# ARC_Lighting_v1_2.net
KiCad netlist of a schematic drawn in EAGLE
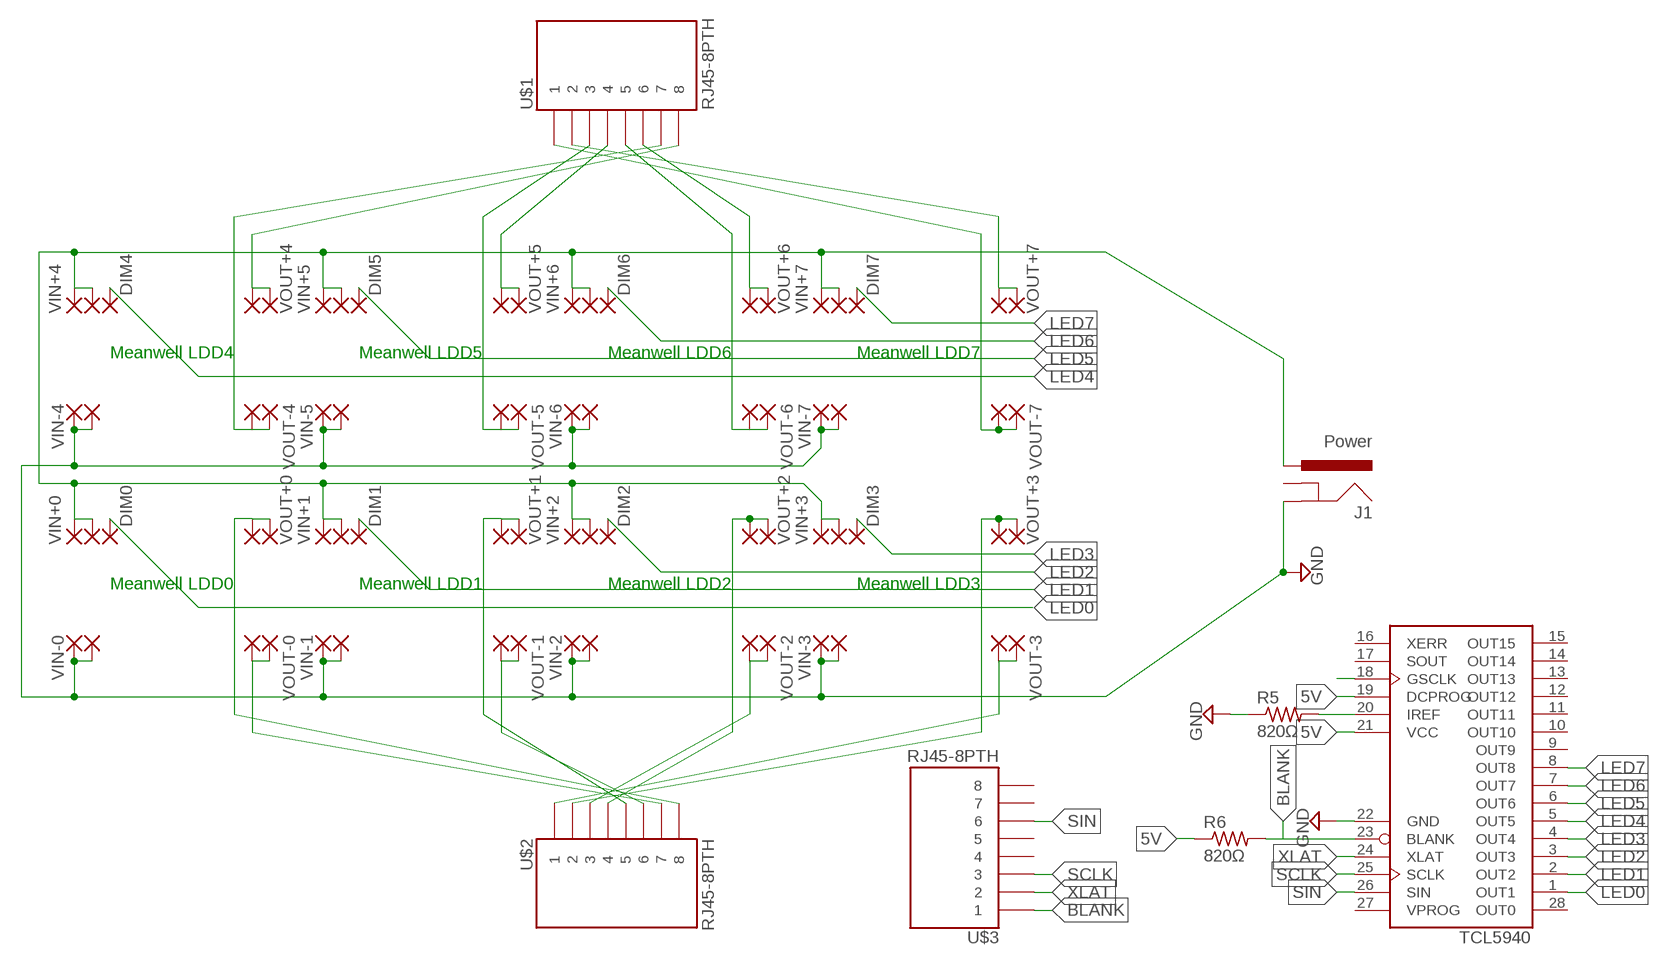
[diagram p0: schematic, sheet 1]

(export (version "E")
  (design (tool "Eeschema 10.0.6"))
  (components
    (comp (ref "DIM0")
      (value "2,15/1,0")
      (footprint "eagle-import:2,15_1,0")
      (libsource (lib "eagle-import") (part "2,15/1,0"))
    )
    (comp (ref "DIM1")
      (value "2,15/1,0")
      (footprint "eagle-import:2,15_1,0")
      (libsource (lib "eagle-import") (part "2,15/1,0"))
    )
    (comp (ref "DIM2")
      (value "2,15/1,0")
      (footprint "eagle-import:2,15_1,0")
      (libsource (lib "eagle-import") (part "2,15/1,0"))
    )
    (comp (ref "DIM3")
      (value "2,15/1,0")
      (footprint "eagle-import:2,15_1,0")
      (libsource (lib "eagle-import") (part "2,15/1,0"))
    )
    (comp (ref "DIM4")
      (value "2,15/1,0")
      (footprint "eagle-import:2,15_1,0")
      (libsource (lib "eagle-import") (part "2,15/1,0"))
    )
    (comp (ref "DIM5")
      (value "2,15/1,0")
      (footprint "eagle-import:2,15_1,0")
      (libsource (lib "eagle-import") (part "2,15/1,0"))
    )
    (comp (ref "DIM6")
      (value "2,15/1,0")
      (footprint "eagle-import:2,15_1,0")
      (libsource (lib "eagle-import") (part "2,15/1,0"))
    )
    (comp (ref "DIM7")
      (value "2,15/1,0")
      (footprint "eagle-import:2,15_1,0")
      (libsource (lib "eagle-import") (part "2,15/1,0"))
    )
    (comp (ref "I+0")
      (value "2,15/1,0")
      (footprint "eagle-import:2,15_1,0")
      (libsource (lib "eagle-import") (part "2,15/1,0"))
    )
    (comp (ref "I+1")
      (value "2,15/1,0")
      (footprint "eagle-import:2,15_1,0")
      (libsource (lib "eagle-import") (part "2,15/1,0"))
    )
    (comp (ref "I+2")
      (value "2,15/1,0")
      (footprint "eagle-import:2,15_1,0")
      (libsource (lib "eagle-import") (part "2,15/1,0"))
    )
    (comp (ref "I+3")
      (value "2,15/1,0")
      (footprint "eagle-import:2,15_1,0")
      (libsource (lib "eagle-import") (part "2,15/1,0"))
    )
    (comp (ref "I+4")
      (value "2,15/1,0")
      (footprint "eagle-import:2,15_1,0")
      (libsource (lib "eagle-import") (part "2,15/1,0"))
    )
    (comp (ref "I+5")
      (value "2,15/1,0")
      (footprint "eagle-import:2,15_1,0")
      (libsource (lib "eagle-import") (part "2,15/1,0"))
    )
    (comp (ref "I+6")
      (value "2,15/1,0")
      (footprint "eagle-import:2,15_1,0")
      (libsource (lib "eagle-import") (part "2,15/1,0"))
    )
    (comp (ref "I+7")
      (value "2,15/1,0")
      (footprint "eagle-import:2,15_1,0")
      (libsource (lib "eagle-import") (part "2,15/1,0"))
    )
    (comp (ref "I-0")
      (value "2,15/1,0")
      (footprint "eagle-import:2,15_1,0")
      (libsource (lib "eagle-import") (part "2,15/1,0"))
    )
    (comp (ref "I-1")
      (value "2,15/1,0")
      (footprint "eagle-import:2,15_1,0")
      (libsource (lib "eagle-import") (part "2,15/1,0"))
    )
    (comp (ref "I-2")
      (value "2,15/1,0")
      (footprint "eagle-import:2,15_1,0")
      (libsource (lib "eagle-import") (part "2,15/1,0"))
    )
    (comp (ref "I-3")
      (value "2,15/1,0")
      (footprint "eagle-import:2,15_1,0")
      (libsource (lib "eagle-import") (part "2,15/1,0"))
    )
    (comp (ref "I-4")
      (value "2,15/1,0")
      (footprint "eagle-import:2,15_1,0")
      (libsource (lib "eagle-import") (part "2,15/1,0"))
    )
    (comp (ref "I-5")
      (value "2,15/1,0")
      (footprint "eagle-import:2,15_1,0")
      (libsource (lib "eagle-import") (part "2,15/1,0"))
    )
    (comp (ref "I-6")
      (value "2,15/1,0")
      (footprint "eagle-import:2,15_1,0")
      (libsource (lib "eagle-import") (part "2,15/1,0"))
    )
    (comp (ref "I-7")
      (value "2,15/1,0")
      (footprint "eagle-import:2,15_1,0")
      (libsource (lib "eagle-import") (part "2,15/1,0"))
    )
    (comp (ref "IC1")
      (value "TCL5940")
      (footprint "eagle-import:DIP28")
      (libsource (lib "eagle-import") (part "TCL5940"))
    )
    (comp (ref "J1")
      (value "Power")
      (footprint "eagle-import:POWER_JACK_PTH_BREAD")
      (libsource (lib "eagle-import") (part "POWER_JACKPTH_BREAD"))
    )
    (comp (ref "O+0")
      (value "2,15/1,0")
      (footprint "eagle-import:2,15_1,0")
      (libsource (lib "eagle-import") (part "2,15/1,0"))
    )
    (comp (ref "O+1")
      (value "2,15/1,0")
      (footprint "eagle-import:2,15_1,0")
      (libsource (lib "eagle-import") (part "2,15/1,0"))
    )
    (comp (ref "O+2")
      (value "2,15/1,0")
      (footprint "eagle-import:2,15_1,0")
      (libsource (lib "eagle-import") (part "2,15/1,0"))
    )
    (comp (ref "O+3")
      (value "2,15/1,0")
      (footprint "eagle-import:2,15_1,0")
      (libsource (lib "eagle-import") (part "2,15/1,0"))
    )
    (comp (ref "O+4")
      (value "2,15/1,0")
      (footprint "eagle-import:2,15_1,0")
      (libsource (lib "eagle-import") (part "2,15/1,0"))
    )
    (comp (ref "O+5")
      (value "2,15/1,0")
      (footprint "eagle-import:2,15_1,0")
      (libsource (lib "eagle-import") (part "2,15/1,0"))
    )
    (comp (ref "O+6")
      (value "2,15/1,0")
      (footprint "eagle-import:2,15_1,0")
      (libsource (lib "eagle-import") (part "2,15/1,0"))
    )
    (comp (ref "O+7")
      (value "2,15/1,0")
      (footprint "eagle-import:2,15_1,0")
      (libsource (lib "eagle-import") (part "2,15/1,0"))
    )
    (comp (ref "O-0")
      (value "2,15/1,0")
      (footprint "eagle-import:2,15_1,0")
      (libsource (lib "eagle-import") (part "2,15/1,0"))
    )
    (comp (ref "O-1")
      (value "2,15/1,0")
      (footprint "eagle-import:2,15_1,0")
      (libsource (lib "eagle-import") (part "2,15/1,0"))
    )
    (comp (ref "O-2")
      (value "2,15/1,0")
      (footprint "eagle-import:2,15_1,0")
      (libsource (lib "eagle-import") (part "2,15/1,0"))
    )
    (comp (ref "O-3")
      (value "2,15/1,0")
      (footprint "eagle-import:2,15_1,0")
      (libsource (lib "eagle-import") (part "2,15/1,0"))
    )
    (comp (ref "O-4")
      (value "2,15/1,0")
      (footprint "eagle-import:2,15_1,0")
      (libsource (lib "eagle-import") (part "2,15/1,0"))
    )
    (comp (ref "O-5")
      (value "2,15/1,0")
      (footprint "eagle-import:2,15_1,0")
      (libsource (lib "eagle-import") (part "2,15/1,0"))
    )
    (comp (ref "O-6")
      (value "2,15/1,0")
      (footprint "eagle-import:2,15_1,0")
      (libsource (lib "eagle-import") (part "2,15/1,0"))
    )
    (comp (ref "O-7")
      (value "2,15/1,0")
      (footprint "eagle-import:2,15_1,0")
      (libsource (lib "eagle-import") (part "2,15/1,0"))
    )
    (comp (ref "R5")
      (value "820Ω")
      (footprint "eagle-import:0204_7")
      (libsource (lib "eagle-import") (part "R-US_0204/7"))
    )
    (comp (ref "R6")
      (value "820Ω")
      (footprint "eagle-import:0204_7")
      (libsource (lib "eagle-import") (part "R-US_0204/7"))
    )
    (comp (ref "U$1")
      (value "RJ45-8PTH")
      (footprint "eagle-import:RJ45-8")
      (libsource (lib "eagle-import") (part "RJ45-8PTH"))
    )
    (comp (ref "U$2")
      (value "RJ45-8PTH")
      (footprint "eagle-import:RJ45-8")
      (libsource (lib "eagle-import") (part "RJ45-8PTH"))
    )
    (comp (ref "U$3")
      (value "RJ45-8PTH")
      (footprint "eagle-import:RJ45-8")
      (libsource (lib "eagle-import") (part "RJ45-8PTH"))
    )
    (comp (ref "VIN+0")
      (value "2,15/1,0")
      (footprint "eagle-import:2,15_1,0")
      (libsource (lib "eagle-import") (part "2,15/1,0"))
    )
    (comp (ref "VIN+1")
      (value "2,15/1,0")
      (footprint "eagle-import:2,15_1,0")
      (libsource (lib "eagle-import") (part "2,15/1,0"))
    )
    (comp (ref "VIN+2")
      (value "2,15/1,0")
      (footprint "eagle-import:2,15_1,0")
      (libsource (lib "eagle-import") (part "2,15/1,0"))
    )
    (comp (ref "VIN+3")
      (value "2,15/1,0")
      (footprint "eagle-import:2,15_1,0")
      (libsource (lib "eagle-import") (part "2,15/1,0"))
    )
    (comp (ref "VIN+4")
      (value "2,15/1,0")
      (footprint "eagle-import:2,15_1,0")
      (libsource (lib "eagle-import") (part "2,15/1,0"))
    )
    (comp (ref "VIN+5")
      (value "2,15/1,0")
      (footprint "eagle-import:2,15_1,0")
      (libsource (lib "eagle-import") (part "2,15/1,0"))
    )
    (comp (ref "VIN+6")
      (value "2,15/1,0")
      (footprint "eagle-import:2,15_1,0")
      (libsource (lib "eagle-import") (part "2,15/1,0"))
    )
    (comp (ref "VIN+7")
      (value "2,15/1,0")
      (footprint "eagle-import:2,15_1,0")
      (libsource (lib "eagle-import") (part "2,15/1,0"))
    )
    (comp (ref "VIN-0")
      (value "2,15/1,0")
      (footprint "eagle-import:2,15_1,0")
      (libsource (lib "eagle-import") (part "2,15/1,0"))
    )
    (comp (ref "VIN-1")
      (value "2,15/1,0")
      (footprint "eagle-import:2,15_1,0")
      (libsource (lib "eagle-import") (part "2,15/1,0"))
    )
    (comp (ref "VIN-2")
      (value "2,15/1,0")
      (footprint "eagle-import:2,15_1,0")
      (libsource (lib "eagle-import") (part "2,15/1,0"))
    )
    (comp (ref "VIN-3")
      (value "2,15/1,0")
      (footprint "eagle-import:2,15_1,0")
      (libsource (lib "eagle-import") (part "2,15/1,0"))
    )
    (comp (ref "VIN-4")
      (value "2,15/1,0")
      (footprint "eagle-import:2,15_1,0")
      (libsource (lib "eagle-import") (part "2,15/1,0"))
    )
    (comp (ref "VIN-5")
      (value "2,15/1,0")
      (footprint "eagle-import:2,15_1,0")
      (libsource (lib "eagle-import") (part "2,15/1,0"))
    )
    (comp (ref "VIN-6")
      (value "2,15/1,0")
      (footprint "eagle-import:2,15_1,0")
      (libsource (lib "eagle-import") (part "2,15/1,0"))
    )
    (comp (ref "VIN-7")
      (value "2,15/1,0")
      (footprint "eagle-import:2,15_1,0")
      (libsource (lib "eagle-import") (part "2,15/1,0"))
    )
    (comp (ref "VOUT+0")
      (value "2,15/1,0")
      (footprint "eagle-import:2,15_1,0")
      (libsource (lib "eagle-import") (part "2,15/1,0"))
    )
    (comp (ref "VOUT+1")
      (value "2,15/1,0")
      (footprint "eagle-import:2,15_1,0")
      (libsource (lib "eagle-import") (part "2,15/1,0"))
    )
    (comp (ref "VOUT+2")
      (value "2,15/1,0")
      (footprint "eagle-import:2,15_1,0")
      (libsource (lib "eagle-import") (part "2,15/1,0"))
    )
    (comp (ref "VOUT+3")
      (value "2,15/1,0")
      (footprint "eagle-import:2,15_1,0")
      (libsource (lib "eagle-import") (part "2,15/1,0"))
    )
    (comp (ref "VOUT+4")
      (value "2,15/1,0")
      (footprint "eagle-import:2,15_1,0")
      (libsource (lib "eagle-import") (part "2,15/1,0"))
    )
    (comp (ref "VOUT+5")
      (value "2,15/1,0")
      (footprint "eagle-import:2,15_1,0")
      (libsource (lib "eagle-import") (part "2,15/1,0"))
    )
    (comp (ref "VOUT+6")
      (value "2,15/1,0")
      (footprint "eagle-import:2,15_1,0")
      (libsource (lib "eagle-import") (part "2,15/1,0"))
    )
    (comp (ref "VOUT+7")
      (value "2,15/1,0")
      (footprint "eagle-import:2,15_1,0")
      (libsource (lib "eagle-import") (part "2,15/1,0"))
    )
    (comp (ref "VOUT-0")
      (value "2,15/1,0")
      (footprint "eagle-import:2,15_1,0")
      (libsource (lib "eagle-import") (part "2,15/1,0"))
    )
    (comp (ref "VOUT-1")
      (value "2,15/1,0")
      (footprint "eagle-import:2,15_1,0")
      (libsource (lib "eagle-import") (part "2,15/1,0"))
    )
    (comp (ref "VOUT-2")
      (value "2,15/1,0")
      (footprint "eagle-import:2,15_1,0")
      (libsource (lib "eagle-import") (part "2,15/1,0"))
    )
    (comp (ref "VOUT-3")
      (value "2,15/1,0")
      (footprint "eagle-import:2,15_1,0")
      (libsource (lib "eagle-import") (part "2,15/1,0"))
    )
    (comp (ref "VOUT-4")
      (value "2,15/1,0")
      (footprint "eagle-import:2,15_1,0")
      (libsource (lib "eagle-import") (part "2,15/1,0"))
    )
    (comp (ref "VOUT-5")
      (value "2,15/1,0")
      (footprint "eagle-import:2,15_1,0")
      (libsource (lib "eagle-import") (part "2,15/1,0"))
    )
    (comp (ref "VOUT-6")
      (value "2,15/1,0")
      (footprint "eagle-import:2,15_1,0")
      (libsource (lib "eagle-import") (part "2,15/1,0"))
    )
    (comp (ref "VOUT-7")
      (value "2,15/1,0")
      (footprint "eagle-import:2,15_1,0")
      (libsource (lib "eagle-import") (part "2,15/1,0"))
    )
  )
  (nets
    (net (code "1") (name "5V") (class "Default")
      (node (ref "IC1") (pin "19") (pinfunction "DCPROG_19") (pintype "input"))
      (node (ref "IC1") (pin "21") (pinfunction "VCC_21") (pintype "power_in"))
      (node (ref "R6") (pin "1") (pinfunction "1_1") (pintype "passive"))
    )
    (net (code "2") (name "BLANK") (class "Default")
      (node (ref "IC1") (pin "23") (pinfunction "BLANK_23") (pintype "input"))
      (node (ref "R6") (pin "2") (pinfunction "2_2") (pintype "passive"))
      (node (ref "U$3") (pin "1") (pinfunction "1_1") (pintype "bidirectional"))
    )
    (net (code "3") (name "GND") (class "Default")
      (node (ref "I-0") (pin "1") (pinfunction "P_1") (pintype "passive"))
      (node (ref "I-1") (pin "1") (pinfunction "P_1") (pintype "passive"))
      (node (ref "I-2") (pin "1") (pinfunction "P_1") (pintype "passive"))
      (node (ref "I-3") (pin "1") (pinfunction "P_1") (pintype "passive"))
      (node (ref "I-4") (pin "1") (pinfunction "P_1") (pintype "passive"))
      (node (ref "I-5") (pin "1") (pinfunction "P_1") (pintype "passive"))
      (node (ref "I-6") (pin "1") (pinfunction "P_1") (pintype "passive"))
      (node (ref "I-7") (pin "1") (pinfunction "P_1") (pintype "passive"))
      (node (ref "IC1") (pin "22") (pinfunction "GND_22") (pintype "power_in"))
      (node (ref "J1") (pin "GND") (pinfunction "GND_GND") (pintype "bidirectional"))
      (node (ref "R5") (pin "1") (pinfunction "1_1") (pintype "passive"))
      (node (ref "VIN-0") (pin "1") (pinfunction "P_1") (pintype "passive"))
      (node (ref "VIN-1") (pin "1") (pinfunction "P_1") (pintype "passive"))
      (node (ref "VIN-2") (pin "1") (pinfunction "P_1") (pintype "passive"))
      (node (ref "VIN-3") (pin "1") (pinfunction "P_1") (pintype "passive"))
      (node (ref "VIN-4") (pin "1") (pinfunction "P_1") (pintype "passive"))
      (node (ref "VIN-5") (pin "1") (pinfunction "P_1") (pintype "passive"))
      (node (ref "VIN-6") (pin "1") (pinfunction "P_1") (pintype "passive"))
      (node (ref "VIN-7") (pin "1") (pinfunction "P_1") (pintype "passive"))
    )
    (net (code "4") (name "LED0") (class "Default")
      (node (ref "DIM0") (pin "1") (pinfunction "P_1") (pintype "passive"))
      (node (ref "IC1") (pin "1") (pinfunction "OUT1_1") (pintype "output"))
    )
    (net (code "5") (name "LED1") (class "Default")
      (node (ref "DIM1") (pin "1") (pinfunction "P_1") (pintype "passive"))
      (node (ref "IC1") (pin "2") (pinfunction "OUT2_2") (pintype "output"))
    )
    (net (code "6") (name "LED2") (class "Default")
      (node (ref "DIM2") (pin "1") (pinfunction "P_1") (pintype "passive"))
      (node (ref "IC1") (pin "3") (pinfunction "OUT3_3") (pintype "output"))
    )
    (net (code "7") (name "LED3") (class "Default")
      (node (ref "DIM3") (pin "1") (pinfunction "P_1") (pintype "passive"))
      (node (ref "IC1") (pin "4") (pinfunction "OUT4_4") (pintype "output"))
    )
    (net (code "8") (name "LED4") (class "Default")
      (node (ref "DIM4") (pin "1") (pinfunction "P_1") (pintype "passive"))
      (node (ref "IC1") (pin "5") (pinfunction "OUT5_5") (pintype "output"))
    )
    (net (code "9") (name "LED5") (class "Default")
      (node (ref "DIM5") (pin "1") (pinfunction "P_1") (pintype "passive"))
      (node (ref "IC1") (pin "6") (pinfunction "OUT6_6") (pintype "output"))
    )
    (net (code "10") (name "LED6") (class "Default")
      (node (ref "DIM6") (pin "1") (pinfunction "P_1") (pintype "passive"))
      (node (ref "IC1") (pin "7") (pinfunction "OUT7_7") (pintype "output"))
    )
    (net (code "11") (name "LED7") (class "Default")
      (node (ref "DIM7") (pin "1") (pinfunction "P_1") (pintype "passive"))
      (node (ref "IC1") (pin "8") (pinfunction "OUT8_8") (pintype "output"))
    )
    (net (code "12") (name "Net-(I+0-P)") (class "Default")
      (node (ref "I+0") (pin "1") (pinfunction "P_1") (pintype "passive"))
      (node (ref "I+1") (pin "1") (pinfunction "P_1") (pintype "passive"))
      (node (ref "I+2") (pin "1") (pinfunction "P_1") (pintype "passive"))
      (node (ref "I+3") (pin "1") (pinfunction "P_1") (pintype "passive"))
      (node (ref "I+4") (pin "1") (pinfunction "P_1") (pintype "passive"))
      (node (ref "I+5") (pin "1") (pinfunction "P_1") (pintype "passive"))
      (node (ref "I+6") (pin "1") (pinfunction "P_1") (pintype "passive"))
      (node (ref "I+7") (pin "1") (pinfunction "P_1") (pintype "passive"))
      (node (ref "J1") (pin "PWR") (pinfunction "PWR_PWR") (pintype "bidirectional"))
      (node (ref "VIN+0") (pin "1") (pinfunction "P_1") (pintype "passive"))
      (node (ref "VIN+1") (pin "1") (pinfunction "P_1") (pintype "passive"))
      (node (ref "VIN+2") (pin "1") (pinfunction "P_1") (pintype "passive"))
      (node (ref "VIN+3") (pin "1") (pinfunction "P_1") (pintype "passive"))
      (node (ref "VIN+4") (pin "1") (pinfunction "P_1") (pintype "passive"))
      (node (ref "VIN+5") (pin "1") (pinfunction "P_1") (pintype "passive"))
      (node (ref "VIN+6") (pin "1") (pinfunction "P_1") (pintype "passive"))
      (node (ref "VIN+7") (pin "1") (pinfunction "P_1") (pintype "passive"))
    )
    (net (code "13") (name "Net-(IC1-IREF)") (class "Default")
      (node (ref "IC1") (pin "20") (pinfunction "IREF_20") (pintype "input"))
      (node (ref "R5") (pin "2") (pinfunction "2_2") (pintype "passive"))
    )
    (net (code "14") (name "Net-(O+0-P)") (class "Default")
      (node (ref "O+0") (pin "1") (pinfunction "P_1") (pintype "passive"))
      (node (ref "U$2") (pin "8") (pinfunction "8_8") (pintype "bidirectional"))
      (node (ref "VOUT+0") (pin "1") (pinfunction "P_1") (pintype "passive"))
    )
    (net (code "15") (name "Net-(O+1-P)") (class "Default")
      (node (ref "O+1") (pin "1") (pinfunction "P_1") (pintype "passive"))
      (node (ref "U$2") (pin "5") (pinfunction "5_5") (pintype "bidirectional"))
      (node (ref "VOUT+1") (pin "1") (pinfunction "P_1") (pintype "passive"))
    )
    (net (code "16") (name "Net-(O+2-P)") (class "Default")
      (node (ref "O+2") (pin "1") (pinfunction "P_1") (pintype "passive"))
      (node (ref "U$2") (pin "4") (pinfunction "4_4") (pintype "bidirectional"))
      (node (ref "VOUT+2") (pin "1") (pinfunction "P_1") (pintype "passive"))
    )
    (net (code "17") (name "Net-(O+3-P)") (class "Default")
      (node (ref "O+3") (pin "1") (pinfunction "P_1") (pintype "passive"))
      (node (ref "U$2") (pin "2") (pinfunction "2_2") (pintype "bidirectional"))
      (node (ref "VOUT+3") (pin "1") (pinfunction "P_1") (pintype "passive"))
    )
    (net (code "18") (name "Net-(O+4-P)") (class "Default")
      (node (ref "O+4") (pin "1") (pinfunction "P_1") (pintype "passive"))
      (node (ref "U$1") (pin "8") (pinfunction "8_8") (pintype "bidirectional"))
      (node (ref "VOUT+4") (pin "1") (pinfunction "P_1") (pintype "passive"))
    )
    (net (code "19") (name "Net-(O+5-P)") (class "Default")
      (node (ref "O+5") (pin "1") (pinfunction "P_1") (pintype "passive"))
      (node (ref "U$1") (pin "4") (pinfunction "4_4") (pintype "bidirectional"))
      (node (ref "VOUT+5") (pin "1") (pinfunction "P_1") (pintype "passive"))
    )
    (net (code "20") (name "Net-(O+6-P)") (class "Default")
      (node (ref "O+6") (pin "1") (pinfunction "P_1") (pintype "passive"))
      (node (ref "U$1") (pin "6") (pinfunction "6_6") (pintype "bidirectional"))
      (node (ref "VOUT+6") (pin "1") (pinfunction "P_1") (pintype "passive"))
    )
    (net (code "21") (name "Net-(O+7-P)") (class "Default")
      (node (ref "O+7") (pin "1") (pinfunction "P_1") (pintype "passive"))
      (node (ref "U$1") (pin "2") (pinfunction "2_2") (pintype "bidirectional"))
      (node (ref "VOUT+7") (pin "1") (pinfunction "P_1") (pintype "passive"))
    )
    (net (code "22") (name "Net-(O-0-P)") (class "Default")
      (node (ref "O-0") (pin "1") (pinfunction "P_1") (pintype "passive"))
      (node (ref "U$2") (pin "7") (pinfunction "7_7") (pintype "bidirectional"))
      (node (ref "VOUT-0") (pin "1") (pinfunction "P_1") (pintype "passive"))
    )
    (net (code "23") (name "Net-(O-1-P)") (class "Default")
      (node (ref "O-1") (pin "1") (pinfunction "P_1") (pintype "passive"))
      (node (ref "U$2") (pin "6") (pinfunction "6_6") (pintype "bidirectional"))
      (node (ref "VOUT-1") (pin "1") (pinfunction "P_1") (pintype "passive"))
    )
    (net (code "24") (name "Net-(O-2-P)") (class "Default")
      (node (ref "O-2") (pin "1") (pinfunction "P_1") (pintype "passive"))
      (node (ref "U$2") (pin "3") (pinfunction "3_3") (pintype "bidirectional"))
      (node (ref "VOUT-2") (pin "1") (pinfunction "P_1") (pintype "passive"))
    )
    (net (code "25") (name "Net-(O-3-P)") (class "Default")
      (node (ref "O-3") (pin "1") (pinfunction "P_1") (pintype "passive"))
      (node (ref "U$2") (pin "1") (pinfunction "1_1") (pintype "bidirectional"))
      (node (ref "VOUT-3") (pin "1") (pinfunction "P_1") (pintype "passive"))
    )
    (net (code "26") (name "Net-(O-4-P)") (class "Default")
      (node (ref "O-4") (pin "1") (pinfunction "P_1") (pintype "passive"))
      (node (ref "U$1") (pin "7") (pinfunction "7_7") (pintype "bidirectional"))
      (node (ref "VOUT-4") (pin "1") (pinfunction "P_1") (pintype "passive"))
    )
    (net (code "27") (name "Net-(O-5-P)") (class "Default")
      (node (ref "O-5") (pin "1") (pinfunction "P_1") (pintype "passive"))
      (node (ref "U$1") (pin "3") (pinfunction "3_3") (pintype "bidirectional"))
      (node (ref "VOUT-5") (pin "1") (pinfunction "P_1") (pintype "passive"))
    )
    (net (code "28") (name "Net-(O-6-P)") (class "Default")
      (node (ref "O-6") (pin "1") (pinfunction "P_1") (pintype "passive"))
      (node (ref "U$1") (pin "5") (pinfunction "5_5") (pintype "bidirectional"))
      (node (ref "VOUT-6") (pin "1") (pinfunction "P_1") (pintype "passive"))
    )
    (net (code "29") (name "Net-(O-7-P)") (class "Default")
      (node (ref "O-7") (pin "1") (pinfunction "P_1") (pintype "passive"))
      (node (ref "U$1") (pin "1") (pinfunction "1_1") (pintype "bidirectional"))
      (node (ref "VOUT-7") (pin "1") (pinfunction "P_1") (pintype "passive"))
    )
    (net (code "30") (name "SCLK") (class "Default")
      (node (ref "IC1") (pin "25") (pinfunction "SCLK_25") (pintype "input"))
      (node (ref "U$3") (pin "3") (pinfunction "3_3") (pintype "bidirectional"))
    )
    (net (code "31") (name "SIN") (class "Default")
      (node (ref "IC1") (pin "26") (pinfunction "SIN_26") (pintype "input"))
      (node (ref "U$3") (pin "6") (pinfunction "6_6") (pintype "bidirectional"))
    )
    (net (code "32") (name "XLAT") (class "Default")
      (node (ref "IC1") (pin "24") (pinfunction "XLAT_24") (pintype "input"))
      (node (ref "U$3") (pin "2") (pinfunction "2_2") (pintype "bidirectional"))
    )
    (net (code "33") (name "unconnected-(IC1-GSCLK-Pad18)") (class "Default")
      (node (ref "IC1") (pin "18") (pinfunction "GSCLK_18") (pintype "input"))
    )
    (net (code "34") (name "unconnected-(IC1-OUT0-Pad28)") (class "Default")
      (node (ref "IC1") (pin "28") (pinfunction "OUT0_28") (pintype "output"))
    )
    (net (code "35") (name "unconnected-(IC1-OUT9-Pad9)") (class "Default")
      (node (ref "IC1") (pin "9") (pinfunction "OUT9_9") (pintype "output"))
    )
    (net (code "36") (name "unconnected-(IC1-OUT10-Pad10)") (class "Default")
      (node (ref "IC1") (pin "10") (pinfunction "OUT10_10") (pintype "output"))
    )
    (net (code "37") (name "unconnected-(IC1-OUT11-Pad11)") (class "Default")
      (node (ref "IC1") (pin "11") (pinfunction "OUT11_11") (pintype "output"))
    )
    (net (code "38") (name "unconnected-(IC1-OUT12-Pad12)") (class "Default")
      (node (ref "IC1") (pin "12") (pinfunction "OUT12_12") (pintype "output"))
    )
    (net (code "39") (name "unconnected-(IC1-OUT13-Pad13)") (class "Default")
      (node (ref "IC1") (pin "13") (pinfunction "OUT13_13") (pintype "output"))
    )
    (net (code "40") (name "unconnected-(IC1-OUT14-Pad14)") (class "Default")
      (node (ref "IC1") (pin "14") (pinfunction "OUT14_14") (pintype "output"))
    )
    (net (code "41") (name "unconnected-(IC1-OUT15-Pad15)") (class "Default")
      (node (ref "IC1") (pin "15") (pinfunction "OUT15_15") (pintype "output"))
    )
    (net (code "42") (name "unconnected-(IC1-SOUT-Pad17)") (class "Default")
      (node (ref "IC1") (pin "17") (pinfunction "SOUT_17") (pintype "output"))
    )
    (net (code "43") (name "unconnected-(IC1-VPROG-Pad27)") (class "Default")
      (node (ref "IC1") (pin "27") (pinfunction "VPROG_27") (pintype "bidirectional"))
    )
    (net (code "44") (name "unconnected-(IC1-XERR-Pad16)") (class "Default")
      (node (ref "IC1") (pin "16") (pinfunction "XERR_16") (pintype "output"))
    )
    (net (code "45") (name "unconnected-(J1-PadGNDBREAK)") (class "Default")
      (node (ref "J1") (pin "GNDBREAK") (pinfunction "GNDBREAK_GNDBREAK") (pintype "bidirectional"))
    )
    (net (code "46") (name "unconnected-(U$3-Pad4)") (class "Default")
      (node (ref "U$3") (pin "4") (pinfunction "4_4") (pintype "bidirectional"))
    )
    (net (code "47") (name "unconnected-(U$3-Pad5)") (class "Default")
      (node (ref "U$3") (pin "5") (pinfunction "5_5") (pintype "bidirectional"))
    )
    (net (code "48") (name "unconnected-(U$3-Pad7)") (class "Default")
      (node (ref "U$3") (pin "7") (pinfunction "7_7") (pintype "bidirectional"))
    )
    (net (code "49") (name "unconnected-(U$3-Pad8)") (class "Default")
      (node (ref "U$3") (pin "8") (pinfunction "8_8") (pintype "bidirectional"))
    )
  )
)
